# WT32SC01-POE_v2.net
KiCad netlist of a schematic drawn in EAGLE
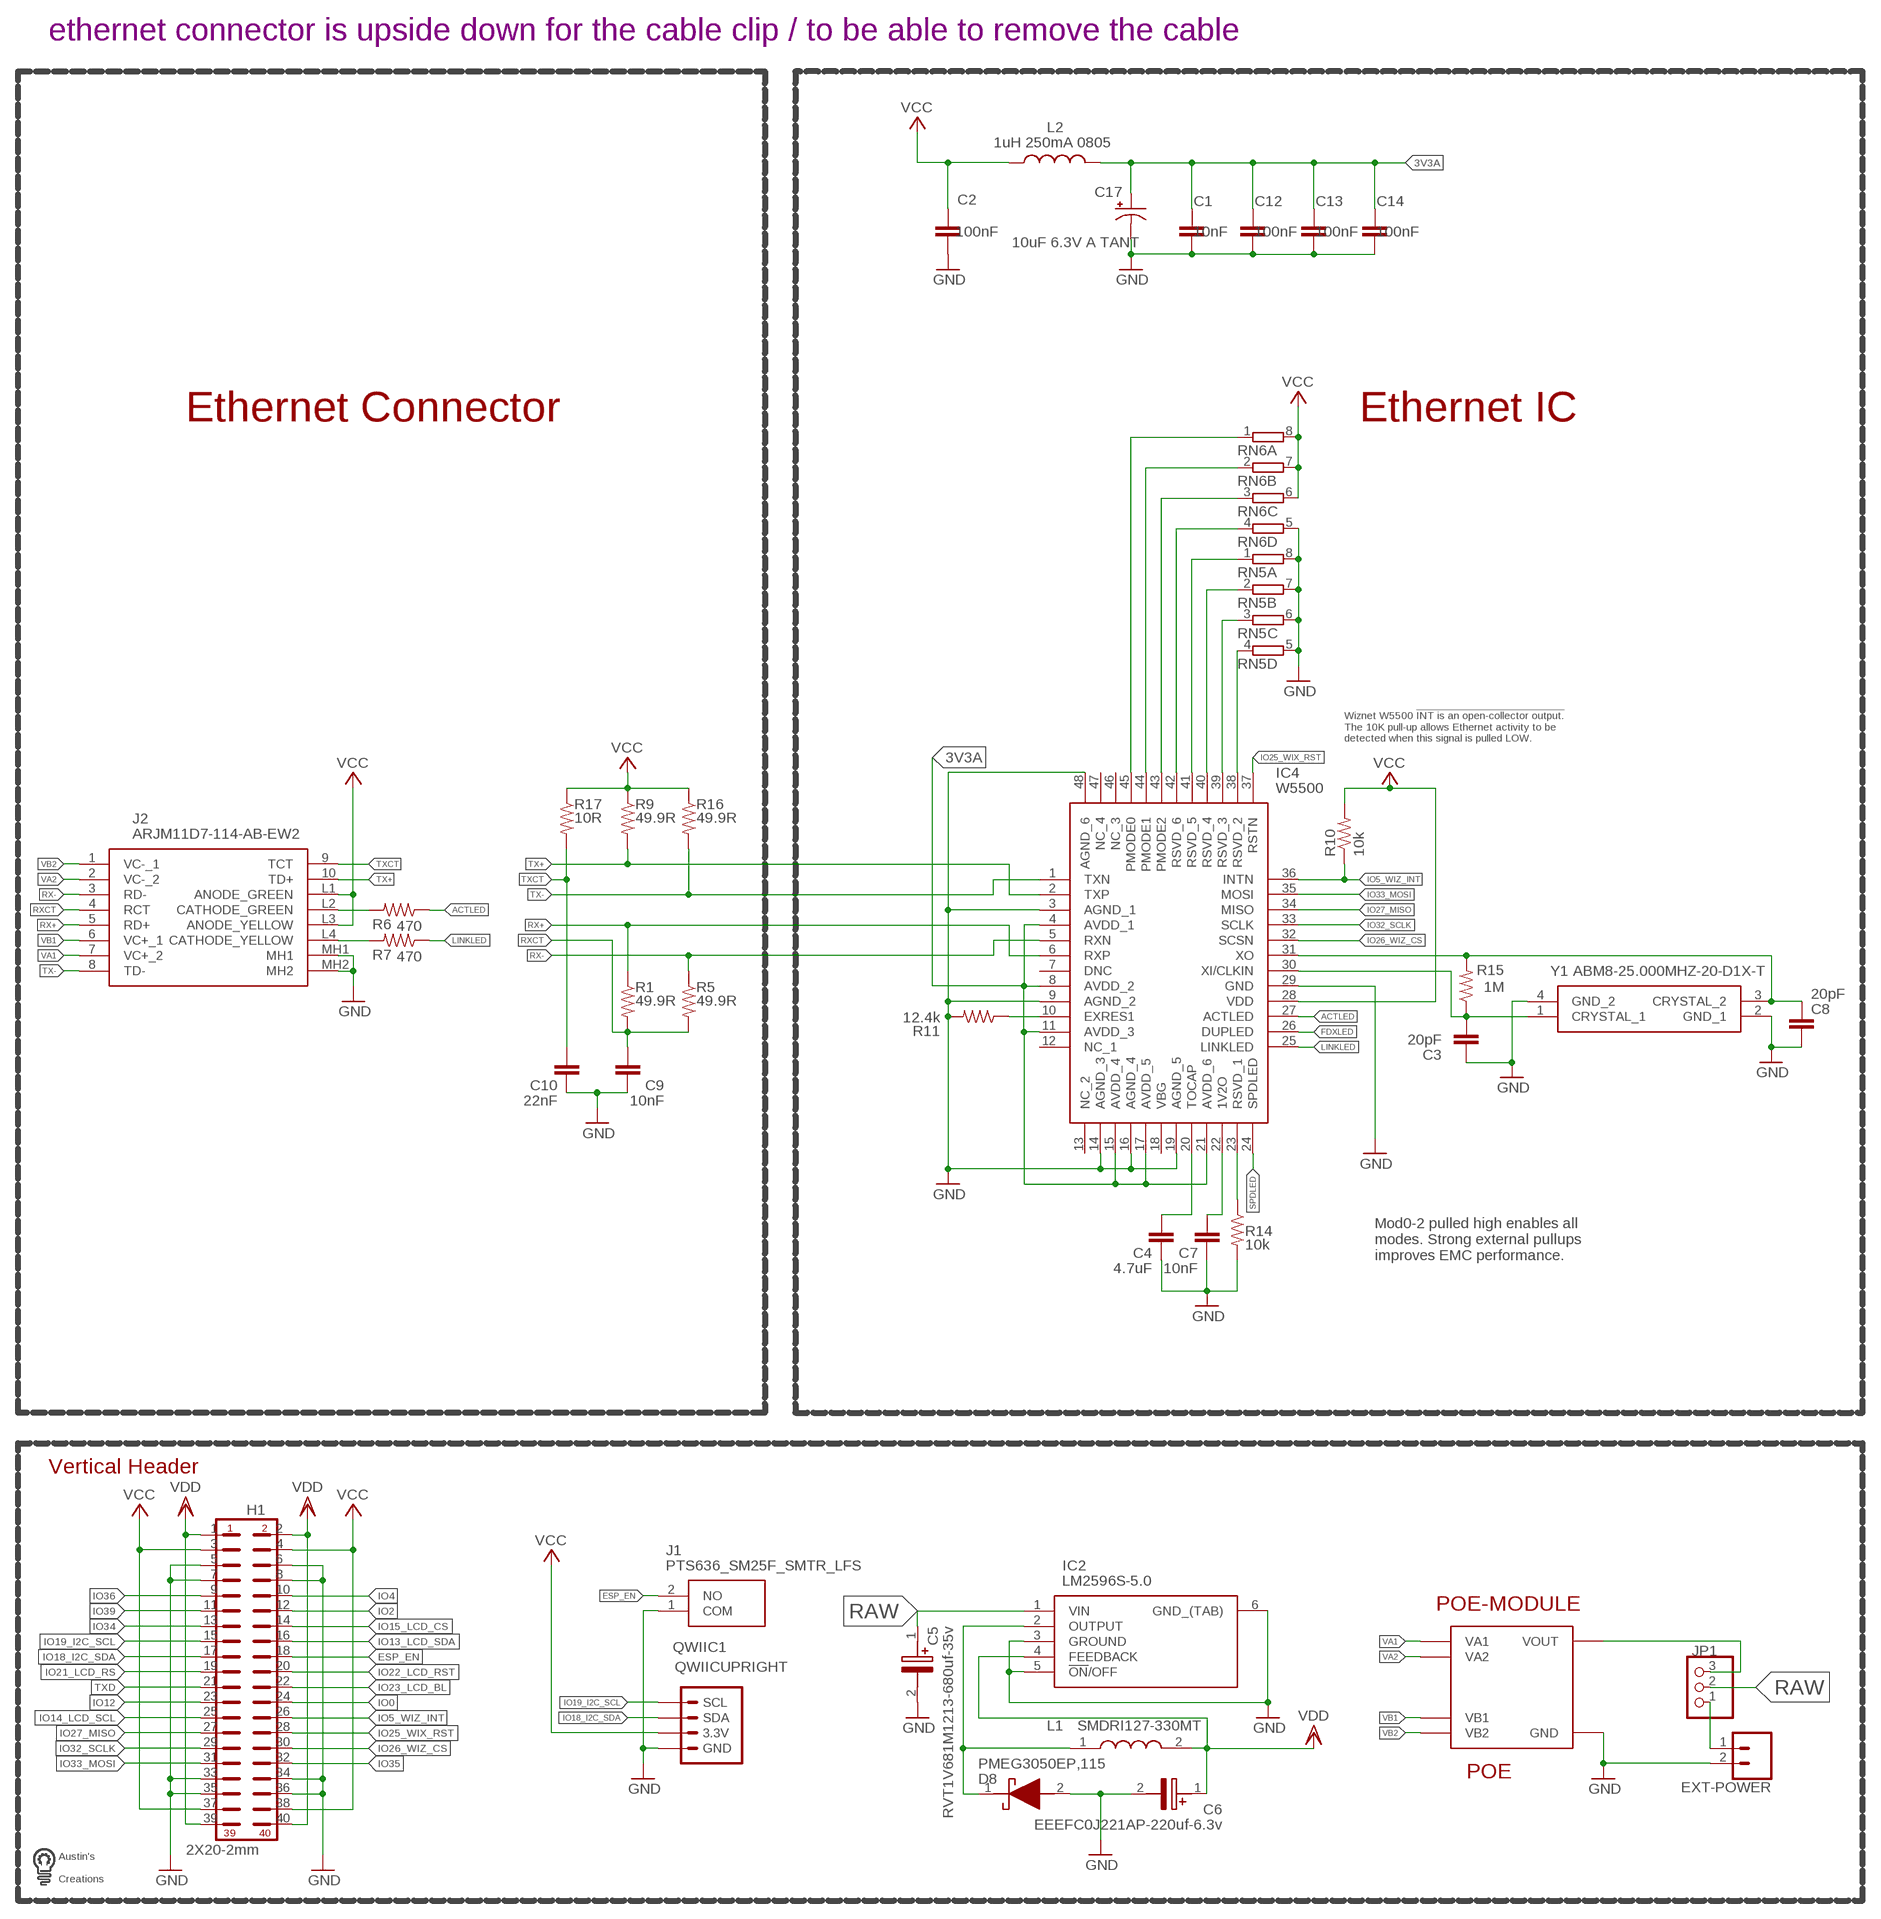
[diagram p0: schematic, sheet 1]

(export (version "E")
  (design (tool "Eeschema 10.0.6"))
  (components
    (comp (ref "C1")
      (value "10nF")
      (footprint "eagle-import:C0603")
      (libsource (lib "eagle-import") (part "C-EUC0603"))
    )
    (comp (ref "C2")
      (value "100nF")
      (footprint "eagle-import:C0603")
      (libsource (lib "eagle-import") (part "C-EUC0603"))
    )
    (comp (ref "C3")
      (value "20pF")
      (footprint "eagle-import:C0603")
      (libsource (lib "eagle-import") (part "resistor_348_C-EUC0603"))
    )
    (comp (ref "C4")
      (value "4.7uF")
      (footprint "eagle-import:C0603")
      (libsource (lib "eagle-import") (part "resistor_348_C-EUC0603"))
    )
    (comp (ref "C5")
      (value "RVT1V681M1213-680uf-35v")
      (footprint "eagle-import:CAPAE1350X1400N")
      (fields
        (field (name "MANUFACTURER_PART_NUMBER") "EEE-HD1V681AQ")
        (field (name "MOUSER_PART_NUMBER") "667-EEE-HD1V681AQ")
      )
      (libsource (lib "eagle-import") (part "EEE-HD1V681AQ"))
    )
    (comp (ref "C6")
      (value "EEEFC0J221AP-220uf-6.3v")
      (footprint "eagle-import:CAPAE830X650N")
      (fields (field (name "MANUFACTURER_PART_NUMBER") "EEEFC0J221AP"))
      (libsource (lib "eagle-import") (part "EEEFC0J221AP"))
    )
    (comp (ref "C7")
      (value "10nF")
      (footprint "eagle-import:C0603")
      (libsource (lib "eagle-import") (part "resistor_348_C-EUC0603"))
    )
    (comp (ref "C8")
      (value "20pF")
      (footprint "eagle-import:C0603")
      (libsource (lib "eagle-import") (part "resistor_348_C-EUC0603"))
    )
    (comp (ref "C9")
      (value "10nF")
      (footprint "eagle-import:C0603")
      (libsource (lib "eagle-import") (part "resistor_348_C-EUC0603"))
    )
    (comp (ref "C10")
      (value "22nF")
      (footprint "eagle-import:C0603")
      (libsource (lib "eagle-import") (part "resistor_348_C-EUC0603"))
    )
    (comp (ref "C12")
      (value "100nF")
      (footprint "eagle-import:C0603")
      (libsource (lib "eagle-import") (part "C-EUC0603"))
    )
    (comp (ref "C13")
      (value "100nF")
      (footprint "eagle-import:C0603")
      (libsource (lib "eagle-import") (part "C-EUC0603"))
    )
    (comp (ref "C14")
      (value "100nF")
      (footprint "eagle-import:C0603")
      (libsource (lib "eagle-import") (part "C-EUC0603"))
    )
    (comp (ref "C17")
      (value "10uF 6.3V A TANT")
      (footprint "eagle-import:A_3216-18W")
      (libsource (lib "eagle-import") (part "CPOL-USA/3216-18W"))
    )
    (comp (ref "D8")
      (value "PMEG3050EP,115")
      (footprint "eagle-import:PMEG3050EP115")
      (fields (field (name "MOUSER_PART_NUMBER") "771-PMEG3050EP115"))
      (libsource (lib "eagle-import") (part "PMEG3050EP,115"))
    )
    (comp (ref "EXT-POWER")
      (value "JL301-50002U02")
      (footprint "eagle-import:SCREWTERMINAL-5MM-2")
      (libsource (lib "eagle-import") (part "2PINBLOCK"))
    )
    (comp (ref "H1")
      (value "2X20-2mm")
      (footprint "eagle-import:2X20-2.00-P-BELOW")
      (libsource (lib "eagle-import") (part "M02X20-2.00-P-BELOW"))
    )
    (comp (ref "IC2")
      (value "LM2596S-5.0")
      (footprint "eagle-import:TO170P1435X465-6N")
      (fields
        (field (name "MANUFACTURER_PART_NUMBER") "LM2596S-3.3/NOPB")
        (field (name "MOUSER_PART_NUMBER") "926-LM2596S-3.3/NOPB")
      )
      (libsource (lib "eagle-import") (part "LM2596S-3.3_NOPB"))
    )
    (comp (ref "IC4")
      (value "W5500")
      (footprint "eagle-import:QFP50P900X900X160-48N")
      (fields (field (name "MOUSER_PART_NUMBER") "950-W5500"))
      (libsource (lib "eagle-import") (part "W5500"))
    )
    (comp (ref "J1")
      (value "PTS636_SM25F_SMTR_LFS")
      (footprint "eagle-import:PTS636SM25FSMTRLFS")
      (fields
        (field (name "ARROW_PART_NUMBER") "PTS636 SM25F SMTR LFS")
        (field (name "MOUSER_PART_NUMBER") "611-PTS636SM25FSMTRL")
      )
      (libsource (lib "eagle-import") (part "PTS636_SM25F_SMTR_LFS"))
    )
    (comp (ref "J2")
      (value "ARJM11D7-114-AB-EW2")
      (footprint "eagle-import:ARJM11D7114ABEW2")
      (fields (field (name "MOUSER_PART_NUMBER") "815-RJM11D7114ABEW2"))
      (libsource (lib "eagle-import") (part "ARJM11D7-114-AB-EW2"))
    )
    (comp (ref "JP1")
      (value "PINHD-1X3")
      (footprint "eagle-import:1X03")
      (libsource (lib "eagle-import") (part "PINHD-1X3"))
    )
    (comp (ref "L1")
      (value "SMDRI127-330MT")
      (footprint "eagle-import:INDPM120120X800N")
      (fields
        (field (name "MANUFACTURER_PART_NUMBER") "CDRH127/LDNP-330MC")
        (field (name "MOUSER_PART_NUMBER") "851-CDRH127LDNP330MC")
      )
      (libsource (lib "eagle-import") (part "CDRH127_LDNP-330MC"))
    )
    (comp (ref "L2")
      (value "1uH 250mA 0805")
      (footprint "eagle-import:L2012C")
      (libsource (lib "eagle-import") (part "L-USL2012C"))
    )
    (comp (ref "POE-MODULE")
      (value "POE")
      (footprint "eagle-import:DP1435")
      (libsource (lib "eagle-import") (part "POE"))
    )
    (comp (ref "QWIIC1")
      (value "QWIICUPRIGHT")
      (footprint "eagle-import:BM04B-SRSS-TB")
      (libsource (lib "eagle-import") (part "QWIICUPRIGHT"))
    )
    (comp (ref "R1")
      (value "49.9R")
      (footprint "eagle-import:R0603")
      (libsource (lib "eagle-import") (part "R-US_R0603"))
    )
    (comp (ref "R5")
      (value "49.9R")
      (footprint "eagle-import:R0603")
      (libsource (lib "eagle-import") (part "R-US_R0603"))
    )
    (comp (ref "R6")
      (value "470")
      (footprint "eagle-import:R0603")
      (libsource (lib "eagle-import") (part "R-US_R0603"))
    )
    (comp (ref "R7")
      (value "470")
      (footprint "eagle-import:R0603")
      (libsource (lib "eagle-import") (part "R-US_R0603"))
    )
    (comp (ref "R9")
      (value "49.9R")
      (footprint "eagle-import:R0603")
      (libsource (lib "eagle-import") (part "R-US_R0603"))
    )
    (comp (ref "R10")
      (value "10k")
      (footprint "eagle-import:R0603")
      (libsource (lib "eagle-import") (part "R-US_R0603"))
    )
    (comp (ref "R11")
      (value "12.4k")
      (footprint "eagle-import:R0603")
      (libsource (lib "eagle-import") (part "R-US_R0603"))
    )
    (comp (ref "R14")
      (value "10k")
      (footprint "eagle-import:R0603")
      (libsource (lib "eagle-import") (part "R-US_R0603"))
    )
    (comp (ref "R15")
      (value "1M")
      (footprint "eagle-import:R0603")
      (libsource (lib "eagle-import") (part "R-US_R0603"))
    )
    (comp (ref "R16")
      (value "49.9R")
      (footprint "eagle-import:R0603")
      (libsource (lib "eagle-import") (part "R-US_R0603"))
    )
    (comp (ref "R17")
      (value "10R")
      (footprint "eagle-import:R0603")
      (libsource (lib "eagle-import") (part "R-US_R0603"))
    )
    (comp (ref "RN5")
      (value "4R-N0603-ARC")
      (footprint "eagle-import:0603-ARC")
      (libsource (lib "eagle-import") (part "4R-N0603-ARC"))
    )
    (comp (ref "RN6")
      (value "4R-N0603-ARC")
      (footprint "eagle-import:0603-ARC")
      (libsource (lib "eagle-import") (part "4R-N0603-ARC"))
    )
    (comp (ref "U$1")
      (value "LOGOMED")
      (footprint "eagle-import:LOGOMED")
      (libsource (lib "eagle-import") (part "LOGOMED"))
    )
    (comp (ref "Y1")
      (value "ABM8-25.000MHZ-20-D1X-T")
      (footprint "eagle-import:ABM825000MHZ10B1UT")
      (fields
        (field (name "MANUFACTURER_PART_NUMBER") "ABM8-25.000MHz-20-D1X-T")
        (field (name "MOUSER_PART_NUMBER") "815-M825000MHZ20D1XT")
      )
      (libsource (lib "eagle-import") (part "ABM8-25.000MHZ-20-D1X-T"))
    )
  )
  (nets
    (net (code "1") (name "3V3A") (class "Default")
      (node (ref "C1") (pin "1") (pinfunction "1_1") (pintype "passive"))
      (node (ref "C12") (pin "1") (pinfunction "1_1") (pintype "passive"))
      (node (ref "C13") (pin "1") (pinfunction "1_1") (pintype "passive"))
      (node (ref "C14") (pin "1") (pinfunction "1_1") (pintype "passive"))
      (node (ref "C17") (pin "+") (pinfunction "+_+") (pintype "passive"))
      (node (ref "IC4") (pin "11") (pinfunction "AVDD_3_11") (pintype "bidirectional"))
      (node (ref "IC4") (pin "15") (pinfunction "AVDD_4_15") (pintype "bidirectional"))
      (node (ref "IC4") (pin "17") (pinfunction "AVDD_5_17") (pintype "bidirectional"))
      (node (ref "IC4") (pin "21") (pinfunction "AVDD_6_21") (pintype "bidirectional"))
      (node (ref "IC4") (pin "4") (pinfunction "AVDD_1_4") (pintype "bidirectional"))
      (node (ref "IC4") (pin "8") (pinfunction "AVDD_2_8") (pintype "bidirectional"))
      (node (ref "L2") (pin "2") (pinfunction "2_2") (pintype "passive"))
    )
    (net (code "2") (name "ACTLED") (class "Default")
      (node (ref "IC4") (pin "27") (pinfunction "ACTLED_27") (pintype "bidirectional"))
      (node (ref "R6") (pin "1") (pinfunction "1_1") (pintype "passive"))
    )
    (net (code "3") (name "ESP_EN") (class "Default")
      (node (ref "H1") (pin "18") (pinfunction "18_18") (pintype "passive"))
      (node (ref "J1") (pin "2") (pinfunction "NO_2") (pintype "bidirectional"))
    )
    (net (code "4") (name "FDXLED") (class "Default")
      (node (ref "IC4") (pin "26") (pinfunction "DUPLED_26") (pintype "bidirectional"))
    )
    (net (code "5") (name "GND") (class "Default")
      (node (ref "C1") (pin "2") (pinfunction "2_2") (pintype "passive"))
      (node (ref "C10") (pin "1") (pinfunction "1_1") (pintype "passive"))
      (node (ref "C12") (pin "2") (pinfunction "2_2") (pintype "passive"))
      (node (ref "C13") (pin "2") (pinfunction "2_2") (pintype "passive"))
      (node (ref "C14") (pin "2") (pinfunction "2_2") (pintype "passive"))
      (node (ref "C17") (pin "-") (pinfunction "-_-") (pintype "passive"))
      (node (ref "C2") (pin "2") (pinfunction "2_2") (pintype "passive"))
      (node (ref "C3") (pin "1") (pinfunction "1_1") (pintype "passive"))
      (node (ref "C4") (pin "1") (pinfunction "1_1") (pintype "passive"))
      (node (ref "C5") (pin "2") (pinfunction "-_2") (pintype "bidirectional"))
      (node (ref "C6") (pin "2") (pinfunction "-_2") (pintype "bidirectional"))
      (node (ref "C7") (pin "1") (pinfunction "1_1") (pintype "passive"))
      (node (ref "C8") (pin "1") (pinfunction "1_1") (pintype "passive"))
      (node (ref "C9") (pin "1") (pinfunction "1_1") (pintype "passive"))
      (node (ref "D8") (pin "2") (pinfunction "A_2") (pintype "bidirectional"))
      (node (ref "EXT-POWER") (pin "2") (pinfunction "2_2") (pintype "passive"))
      (node (ref "H1") (pin "33") (pinfunction "33_33") (pintype "passive"))
      (node (ref "H1") (pin "34") (pinfunction "34_34") (pintype "passive"))
      (node (ref "H1") (pin "35") (pinfunction "35_35") (pintype "passive"))
      (node (ref "H1") (pin "36") (pinfunction "36_36") (pintype "passive"))
      (node (ref "H1") (pin "5") (pinfunction "5_5") (pintype "passive"))
      (node (ref "H1") (pin "6") (pinfunction "6_6") (pintype "passive"))
      (node (ref "H1") (pin "7") (pinfunction "7_7") (pintype "passive"))
      (node (ref "H1") (pin "8") (pinfunction "8_8") (pintype "passive"))
      (node (ref "IC2") (pin "3") (pinfunction "GROUND_3") (pintype "bidirectional"))
      (node (ref "IC2") (pin "5") (pinfunction "~{ON}/OFF_5") (pintype "bidirectional"))
      (node (ref "IC2") (pin "6") (pinfunction "GND_(TAB)_6") (pintype "power_in"))
      (node (ref "IC4") (pin "14") (pinfunction "AGND_3_14") (pintype "bidirectional"))
      (node (ref "IC4") (pin "16") (pinfunction "AGND_4_16") (pintype "bidirectional"))
      (node (ref "IC4") (pin "19") (pinfunction "AGND_5_19") (pintype "bidirectional"))
      (node (ref "IC4") (pin "29") (pinfunction "GND_29") (pintype "bidirectional"))
      (node (ref "IC4") (pin "3") (pinfunction "AGND_1_3") (pintype "bidirectional"))
      (node (ref "IC4") (pin "48") (pinfunction "AGND_6_48") (pintype "bidirectional"))
      (node (ref "IC4") (pin "9") (pinfunction "AGND_2_9") (pintype "bidirectional"))
      (node (ref "J1") (pin "1") (pinfunction "COM_1") (pintype "bidirectional"))
      (node (ref "J2") (pin "MH1") (pinfunction "MH1_MH1") (pintype "bidirectional"))
      (node (ref "J2") (pin "MH2") (pinfunction "MH2_MH2") (pintype "bidirectional"))
      (node (ref "POE-MODULE") (pin "GND") (pinfunction "GND_GND") (pintype "bidirectional"))
      (node (ref "QWIIC1") (pin "1") (pinfunction "GND_1") (pintype "passive"))
      (node (ref "R11") (pin "2") (pinfunction "2_2") (pintype "passive"))
      (node (ref "R14") (pin "2") (pinfunction "2_2") (pintype "passive"))
      (node (ref "RN5") (pin "5") (pinfunction "2_5") (pintype "passive"))
      (node (ref "RN5") (pin "6") (pinfunction "2_6") (pintype "passive"))
      (node (ref "RN5") (pin "7") (pinfunction "2_7") (pintype "passive"))
      (node (ref "RN5") (pin "8") (pinfunction "2_8") (pintype "passive"))
      (node (ref "RN6") (pin "5") (pinfunction "2_5") (pintype "passive"))
      (node (ref "Y1") (pin "2") (pinfunction "GND_1_2") (pintype "bidirectional"))
      (node (ref "Y1") (pin "4") (pinfunction "GND_2_4") (pintype "bidirectional"))
    )
    (net (code "6") (name "IO0") (class "Default")
      (node (ref "H1") (pin "24") (pinfunction "24_24") (pintype "passive"))
    )
    (net (code "7") (name "IO2") (class "Default")
      (node (ref "H1") (pin "12") (pinfunction "12_12") (pintype "passive"))
    )
    (net (code "8") (name "IO4") (class "Default")
      (node (ref "H1") (pin "10") (pinfunction "10_10") (pintype "passive"))
    )
    (net (code "9") (name "IO5_WIZ_INT") (class "Default")
      (node (ref "H1") (pin "26") (pinfunction "26_26") (pintype "passive"))
      (node (ref "IC4") (pin "36") (pinfunction "INTN_36") (pintype "bidirectional"))
      (node (ref "R10") (pin "1") (pinfunction "1_1") (pintype "passive"))
    )
    (net (code "10") (name "IO12") (class "Default")
      (node (ref "H1") (pin "23") (pinfunction "23_23") (pintype "passive"))
    )
    (net (code "11") (name "IO13_LCD_SDA") (class "Default")
      (node (ref "H1") (pin "16") (pinfunction "16_16") (pintype "passive"))
    )
    (net (code "12") (name "IO14_LCD_SCL") (class "Default")
      (node (ref "H1") (pin "25") (pinfunction "25_25") (pintype "passive"))
    )
    (net (code "13") (name "IO15_LCD_CS") (class "Default")
      (node (ref "H1") (pin "14") (pinfunction "14_14") (pintype "passive"))
    )
    (net (code "14") (name "IO18_I2C_SDA") (class "Default")
      (node (ref "H1") (pin "17") (pinfunction "17_17") (pintype "passive"))
      (node (ref "QWIIC1") (pin "3") (pinfunction "SDA_3") (pintype "passive"))
    )
    (net (code "15") (name "IO19_I2C_SCL") (class "Default")
      (node (ref "H1") (pin "15") (pinfunction "15_15") (pintype "passive"))
      (node (ref "QWIIC1") (pin "4") (pinfunction "SCL_4") (pintype "passive"))
    )
    (net (code "16") (name "IO21_LCD_RS") (class "Default")
      (node (ref "H1") (pin "19") (pinfunction "19_19") (pintype "passive"))
    )
    (net (code "17") (name "IO22_LCD_RST") (class "Default")
      (node (ref "H1") (pin "20") (pinfunction "20_20") (pintype "passive"))
    )
    (net (code "18") (name "IO23_LCD_BL") (class "Default")
      (node (ref "H1") (pin "22") (pinfunction "22_22") (pintype "passive"))
    )
    (net (code "19") (name "IO25_WIX_RST") (class "Default")
      (node (ref "H1") (pin "28") (pinfunction "28_28") (pintype "passive"))
      (node (ref "IC4") (pin "37") (pinfunction "RSTN_37") (pintype "bidirectional"))
    )
    (net (code "20") (name "IO26_WIZ_CS") (class "Default")
      (node (ref "H1") (pin "30") (pinfunction "30_30") (pintype "passive"))
      (node (ref "IC4") (pin "32") (pinfunction "SCSN_32") (pintype "bidirectional"))
    )
    (net (code "21") (name "IO27_MISO") (class "Default")
      (node (ref "H1") (pin "27") (pinfunction "27_27") (pintype "passive"))
      (node (ref "IC4") (pin "34") (pinfunction "MISO_34") (pintype "bidirectional"))
    )
    (net (code "22") (name "IO32_SCLK") (class "Default")
      (node (ref "H1") (pin "29") (pinfunction "29_29") (pintype "passive"))
      (node (ref "IC4") (pin "33") (pinfunction "SCLK_33") (pintype "bidirectional"))
    )
    (net (code "23") (name "IO33_MOSI") (class "Default")
      (node (ref "H1") (pin "31") (pinfunction "31_31") (pintype "passive"))
      (node (ref "IC4") (pin "35") (pinfunction "MOSI_35") (pintype "bidirectional"))
    )
    (net (code "24") (name "IO34") (class "Default")
      (node (ref "H1") (pin "13") (pinfunction "13_13") (pintype "passive"))
    )
    (net (code "25") (name "IO35") (class "Default")
      (node (ref "H1") (pin "32") (pinfunction "32_32") (pintype "passive"))
    )
    (net (code "26") (name "IO36") (class "Default")
      (node (ref "H1") (pin "9") (pinfunction "9_9") (pintype "passive"))
    )
    (net (code "27") (name "IO39") (class "Default")
      (node (ref "H1") (pin "11") (pinfunction "11_11") (pintype "passive"))
    )
    (net (code "28") (name "LINKLED") (class "Default")
      (node (ref "IC4") (pin "25") (pinfunction "LINKLED_25") (pintype "bidirectional"))
      (node (ref "R7") (pin "1") (pinfunction "1_1") (pintype "passive"))
    )
    (net (code "29") (name "Net-(D8-K)") (class "Default")
      (node (ref "D8") (pin "1") (pinfunction "K_1") (pintype "bidirectional"))
      (node (ref "IC2") (pin "2") (pinfunction "OUTPUT_2") (pintype "output"))
      (node (ref "L1") (pin "1") (pinfunction "1_1") (pintype "bidirectional"))
    )
    (net (code "30") (name "Net-(EXT-POWER-Pad1)") (class "Default")
      (node (ref "EXT-POWER") (pin "1") (pinfunction "1_1") (pintype "passive"))
      (node (ref "JP1") (pin "1") (pinfunction "1_1") (pintype "passive"))
    )
    (net (code "31") (name "Net-(IC4-1V2O)") (class "Default")
      (node (ref "C7") (pin "2") (pinfunction "2_2") (pintype "passive"))
      (node (ref "IC4") (pin "22") (pinfunction "1V2O_22") (pintype "bidirectional"))
    )
    (net (code "32") (name "Net-(IC4-EXRES1)") (class "Default")
      (node (ref "IC4") (pin "10") (pinfunction "EXRES1_10") (pintype "bidirectional"))
      (node (ref "R11") (pin "1") (pinfunction "1_1") (pintype "passive"))
    )
    (net (code "33") (name "Net-(IC4-PMODE0)") (class "Default")
      (node (ref "IC4") (pin "45") (pinfunction "PMODE0_45") (pintype "bidirectional"))
      (node (ref "RN6") (pin "1") (pinfunction "1_1") (pintype "passive"))
    )
    (net (code "34") (name "Net-(IC4-PMODE1)") (class "Default")
      (node (ref "IC4") (pin "44") (pinfunction "PMODE1_44") (pintype "bidirectional"))
      (node (ref "RN6") (pin "2") (pinfunction "1_2") (pintype "passive"))
    )
    (net (code "35") (name "Net-(IC4-PMODE2)") (class "Default")
      (node (ref "IC4") (pin "43") (pinfunction "PMODE2_43") (pintype "bidirectional"))
      (node (ref "RN6") (pin "3") (pinfunction "1_3") (pintype "passive"))
    )
    (net (code "36") (name "Net-(IC4-RSVD_1)") (class "Default")
      (node (ref "IC4") (pin "23") (pinfunction "RSVD_1_23") (pintype "bidirectional"))
      (node (ref "R14") (pin "1") (pinfunction "1_1") (pintype "passive"))
    )
    (net (code "37") (name "Net-(IC4-RSVD_2)") (class "Default")
      (node (ref "IC4") (pin "38") (pinfunction "RSVD_2_38") (pintype "bidirectional"))
      (node (ref "RN5") (pin "4") (pinfunction "1_4") (pintype "passive"))
    )
    (net (code "38") (name "Net-(IC4-RSVD_3)") (class "Default")
      (node (ref "IC4") (pin "39") (pinfunction "RSVD_3_39") (pintype "bidirectional"))
      (node (ref "RN5") (pin "3") (pinfunction "1_3") (pintype "passive"))
    )
    (net (code "39") (name "Net-(IC4-RSVD_4)") (class "Default")
      (node (ref "IC4") (pin "40") (pinfunction "RSVD_4_40") (pintype "bidirectional"))
      (node (ref "RN5") (pin "2") (pinfunction "1_2") (pintype "passive"))
    )
    (net (code "40") (name "Net-(IC4-RSVD_5)") (class "Default")
      (node (ref "IC4") (pin "41") (pinfunction "RSVD_5_41") (pintype "bidirectional"))
      (node (ref "RN5") (pin "1") (pinfunction "1_1") (pintype "passive"))
    )
    (net (code "41") (name "Net-(IC4-RSVD_6)") (class "Default")
      (node (ref "IC4") (pin "42") (pinfunction "RSVD_6_42") (pintype "bidirectional"))
      (node (ref "RN6") (pin "4") (pinfunction "1_4") (pintype "passive"))
    )
    (net (code "42") (name "Net-(IC4-TOCAP)") (class "Default")
      (node (ref "C4") (pin "2") (pinfunction "2_2") (pintype "passive"))
      (node (ref "IC4") (pin "20") (pinfunction "TOCAP_20") (pintype "bidirectional"))
    )
    (net (code "43") (name "Net-(IC4-XI{slash}CLKIN)") (class "Default")
      (node (ref "C3") (pin "2") (pinfunction "2_2") (pintype "passive"))
      (node (ref "IC4") (pin "30") (pinfunction "XI/CLKIN_30") (pintype "bidirectional"))
      (node (ref "R15") (pin "1") (pinfunction "1_1") (pintype "passive"))
      (node (ref "Y1") (pin "1") (pinfunction "CRYSTAL_1_1") (pintype "bidirectional"))
    )
    (net (code "44") (name "Net-(IC4-XO)") (class "Default")
      (node (ref "C8") (pin "2") (pinfunction "2_2") (pintype "passive"))
      (node (ref "IC4") (pin "31") (pinfunction "XO_31") (pintype "bidirectional"))
      (node (ref "R15") (pin "2") (pinfunction "2_2") (pintype "passive"))
      (node (ref "Y1") (pin "3") (pinfunction "CRYSTAL_2_3") (pintype "bidirectional"))
    )
    (net (code "45") (name "Net-(J2-CATHODE_GREEN)") (class "Default")
      (node (ref "J2") (pin "L2") (pinfunction "CATHODE_GREEN_L2") (pintype "bidirectional"))
      (node (ref "R6") (pin "2") (pinfunction "2_2") (pintype "passive"))
    )
    (net (code "46") (name "Net-(J2-CATHODE_YELLOW)") (class "Default")
      (node (ref "J2") (pin "L4") (pinfunction "CATHODE_YELLOW_L4") (pintype "bidirectional"))
      (node (ref "R7") (pin "2") (pinfunction "2_2") (pintype "passive"))
    )
    (net (code "47") (name "Net-(JP1-Pad3)") (class "Default")
      (node (ref "JP1") (pin "3") (pinfunction "3_3") (pintype "passive"))
      (node (ref "POE-MODULE") (pin "VOUT") (pinfunction "VOUT_VOUT") (pintype "bidirectional"))
    )
    (net (code "48") (name "RAW") (class "Default")
      (node (ref "C5") (pin "1") (pinfunction "+_1") (pintype "bidirectional"))
      (node (ref "IC2") (pin "1") (pinfunction "VIN_1") (pintype "input"))
      (node (ref "JP1") (pin "2") (pinfunction "2_2") (pintype "passive"))
    )
    (net (code "49") (name "RX+") (class "Default")
      (node (ref "IC4") (pin "6") (pinfunction "RXP_6") (pintype "bidirectional"))
      (node (ref "J2") (pin "5") (pinfunction "RD+_5") (pintype "bidirectional"))
      (node (ref "R1") (pin "1") (pinfunction "1_1") (pintype "passive"))
    )
    (net (code "50") (name "RX-") (class "Default")
      (node (ref "IC4") (pin "5") (pinfunction "RXN_5") (pintype "bidirectional"))
      (node (ref "J2") (pin "3") (pinfunction "RD-_3") (pintype "bidirectional"))
      (node (ref "R5") (pin "1") (pinfunction "1_1") (pintype "passive"))
    )
    (net (code "51") (name "RXCT") (class "Default")
      (node (ref "C9") (pin "2") (pinfunction "2_2") (pintype "passive"))
      (node (ref "J2") (pin "4") (pinfunction "RCT_4") (pintype "bidirectional"))
      (node (ref "R1") (pin "2") (pinfunction "2_2") (pintype "passive"))
      (node (ref "R5") (pin "2") (pinfunction "2_2") (pintype "passive"))
    )
    (net (code "52") (name "SPDLED") (class "Default")
      (node (ref "IC4") (pin "24") (pinfunction "SPDLED_24") (pintype "bidirectional"))
    )
    (net (code "53") (name "TX+") (class "Default")
      (node (ref "IC4") (pin "2") (pinfunction "TXP_2") (pintype "bidirectional"))
      (node (ref "J2") (pin "10") (pinfunction "TD+_10") (pintype "bidirectional"))
      (node (ref "R9") (pin "2") (pinfunction "2_2") (pintype "passive"))
    )
    (net (code "54") (name "TX-") (class "Default")
      (node (ref "IC4") (pin "1") (pinfunction "TXN_1") (pintype "bidirectional"))
      (node (ref "J2") (pin "8") (pinfunction "TD-_8") (pintype "bidirectional"))
      (node (ref "R16") (pin "2") (pinfunction "2_2") (pintype "passive"))
    )
    (net (code "55") (name "TXCT") (class "Default")
      (node (ref "C10") (pin "2") (pinfunction "2_2") (pintype "passive"))
      (node (ref "J2") (pin "9") (pinfunction "TCT_9") (pintype "bidirectional"))
      (node (ref "R17") (pin "2") (pinfunction "2_2") (pintype "passive"))
    )
    (net (code "56") (name "TXD") (class "Default")
      (node (ref "H1") (pin "21") (pinfunction "21_21") (pintype "passive"))
    )
    (net (code "57") (name "VA1") (class "Default")
      (node (ref "J2") (pin "7") (pinfunction "VC+_2_7") (pintype "bidirectional"))
      (node (ref "POE-MODULE") (pin "VA1") (pinfunction "VA1_VA1") (pintype "bidirectional"))
    )
    (net (code "58") (name "VA2") (class "Default")
      (node (ref "J2") (pin "2") (pinfunction "VC-_2_2") (pintype "bidirectional"))
      (node (ref "POE-MODULE") (pin "VA2") (pinfunction "VA2_VA2") (pintype "bidirectional"))
    )
    (net (code "59") (name "VB1") (class "Default")
      (node (ref "J2") (pin "6") (pinfunction "VC+_1_6") (pintype "bidirectional"))
      (node (ref "POE-MODULE") (pin "VB1") (pinfunction "VB1_VB1") (pintype "bidirectional"))
    )
    (net (code "60") (name "VB2") (class "Default")
      (node (ref "J2") (pin "1") (pinfunction "VC-_1_1") (pintype "bidirectional"))
      (node (ref "POE-MODULE") (pin "VB2") (pinfunction "VB2_VB2") (pintype "bidirectional"))
    )
    (net (code "61") (name "VCC") (class "Default")
      (node (ref "C2") (pin "1") (pinfunction "1_1") (pintype "passive"))
      (node (ref "H1") (pin "3") (pinfunction "3_3") (pintype "passive"))
      (node (ref "H1") (pin "37") (pinfunction "37_37") (pintype "passive"))
      (node (ref "H1") (pin "38") (pinfunction "38_38") (pintype "passive"))
      (node (ref "H1") (pin "4") (pinfunction "4_4") (pintype "passive"))
      (node (ref "IC4") (pin "28") (pinfunction "VDD_28") (pintype "bidirectional"))
      (node (ref "J2") (pin "L1") (pinfunction "ANODE_GREEN_L1") (pintype "bidirectional"))
      (node (ref "J2") (pin "L3") (pinfunction "ANODE_YELLOW_L3") (pintype "bidirectional"))
      (node (ref "L2") (pin "1") (pinfunction "1_1") (pintype "passive"))
      (node (ref "QWIIC1") (pin "2") (pinfunction "3.3V_2") (pintype "passive"))
      (node (ref "R10") (pin "2") (pinfunction "2_2") (pintype "passive"))
      (node (ref "R16") (pin "1") (pinfunction "1_1") (pintype "passive"))
      (node (ref "R17") (pin "1") (pinfunction "1_1") (pintype "passive"))
      (node (ref "R9") (pin "1") (pinfunction "1_1") (pintype "passive"))
      (node (ref "RN6") (pin "6") (pinfunction "2_6") (pintype "passive"))
      (node (ref "RN6") (pin "7") (pinfunction "2_7") (pintype "passive"))
      (node (ref "RN6") (pin "8") (pinfunction "2_8") (pintype "passive"))
    )
    (net (code "62") (name "VDD") (class "Default")
      (node (ref "C6") (pin "1") (pinfunction "+_1") (pintype "bidirectional"))
      (node (ref "H1") (pin "1") (pinfunction "1_1") (pintype "passive"))
      (node (ref "H1") (pin "2") (pinfunction "2_2") (pintype "passive"))
      (node (ref "H1") (pin "39") (pinfunction "39_39") (pintype "passive"))
      (node (ref "H1") (pin "40") (pinfunction "40_40") (pintype "passive"))
      (node (ref "IC2") (pin "4") (pinfunction "FEEDBACK_4") (pintype "bidirectional"))
      (node (ref "L1") (pin "2") (pinfunction "2_2") (pintype "bidirectional"))
    )
    (net (code "63") (name "unconnected-(IC4-DNC-Pad7)") (class "Default")
      (node (ref "IC4") (pin "7") (pinfunction "DNC_7") (pintype "bidirectional"))
    )
    (net (code "64") (name "unconnected-(IC4-NC_1-Pad12)") (class "Default")
      (node (ref "IC4") (pin "12") (pinfunction "NC_1_12") (pintype "bidirectional"))
    )
    (net (code "65") (name "unconnected-(IC4-NC_2-Pad13)") (class "Default")
      (node (ref "IC4") (pin "13") (pinfunction "NC_2_13") (pintype "bidirectional"))
    )
    (net (code "66") (name "unconnected-(IC4-NC_3-Pad46)") (class "Default")
      (node (ref "IC4") (pin "46") (pinfunction "NC_3_46") (pintype "bidirectional"))
    )
    (net (code "67") (name "unconnected-(IC4-NC_4-Pad47)") (class "Default")
      (node (ref "IC4") (pin "47") (pinfunction "NC_4_47") (pintype "bidirectional"))
    )
    (net (code "68") (name "unconnected-(IC4-VBG-Pad18)") (class "Default")
      (node (ref "IC4") (pin "18") (pinfunction "VBG_18") (pintype "bidirectional"))
    )
  )
)
